# RP_Watchy.net
KiCad netlist of a schematic drawn in EAGLE
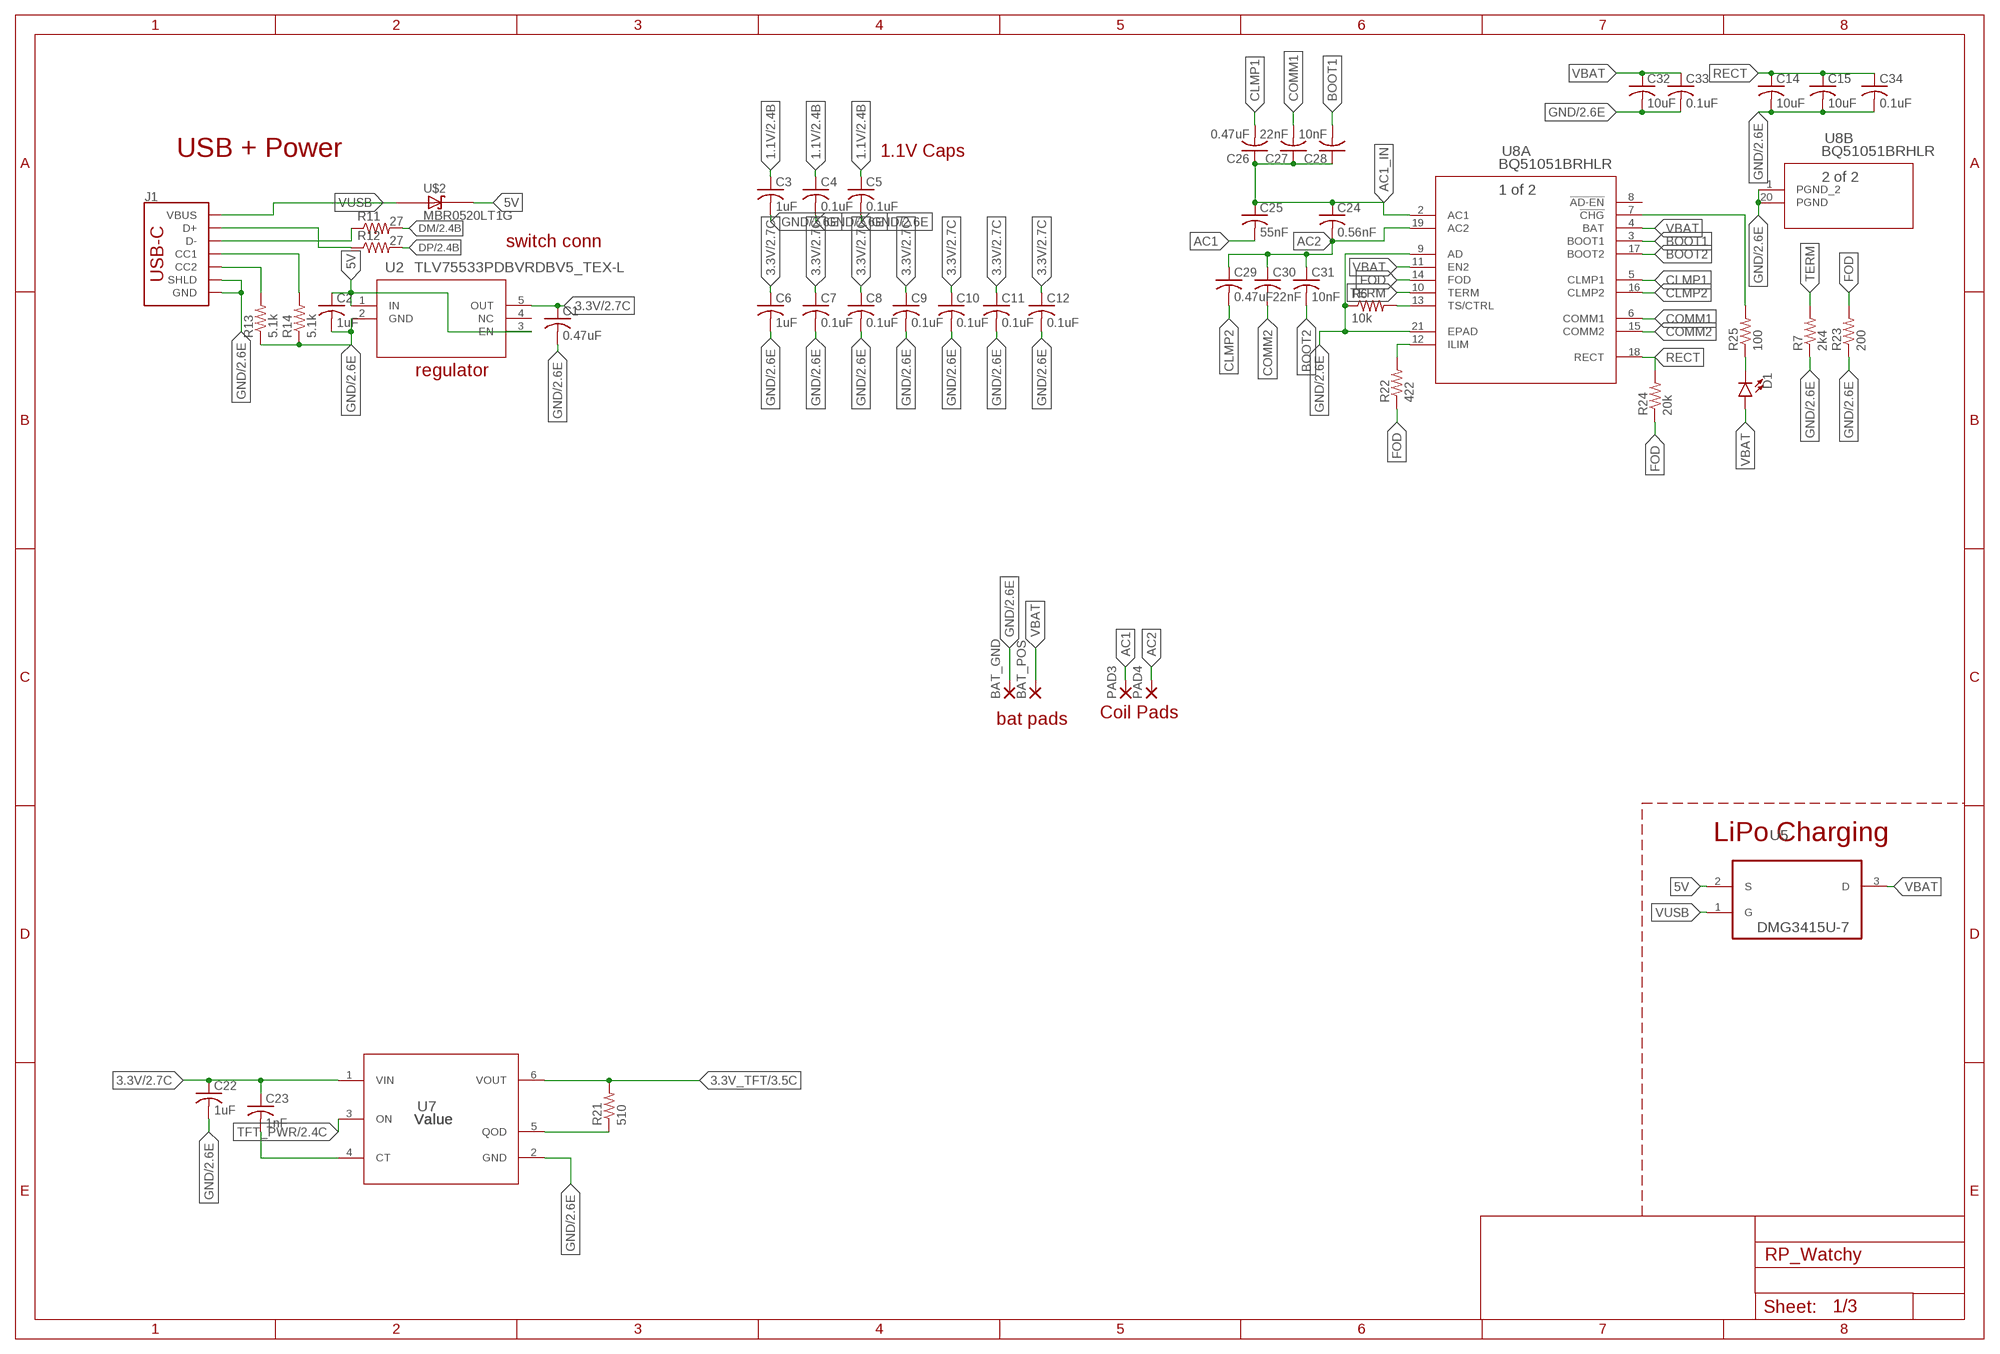
[diagram p0: schematic, sheet 1]
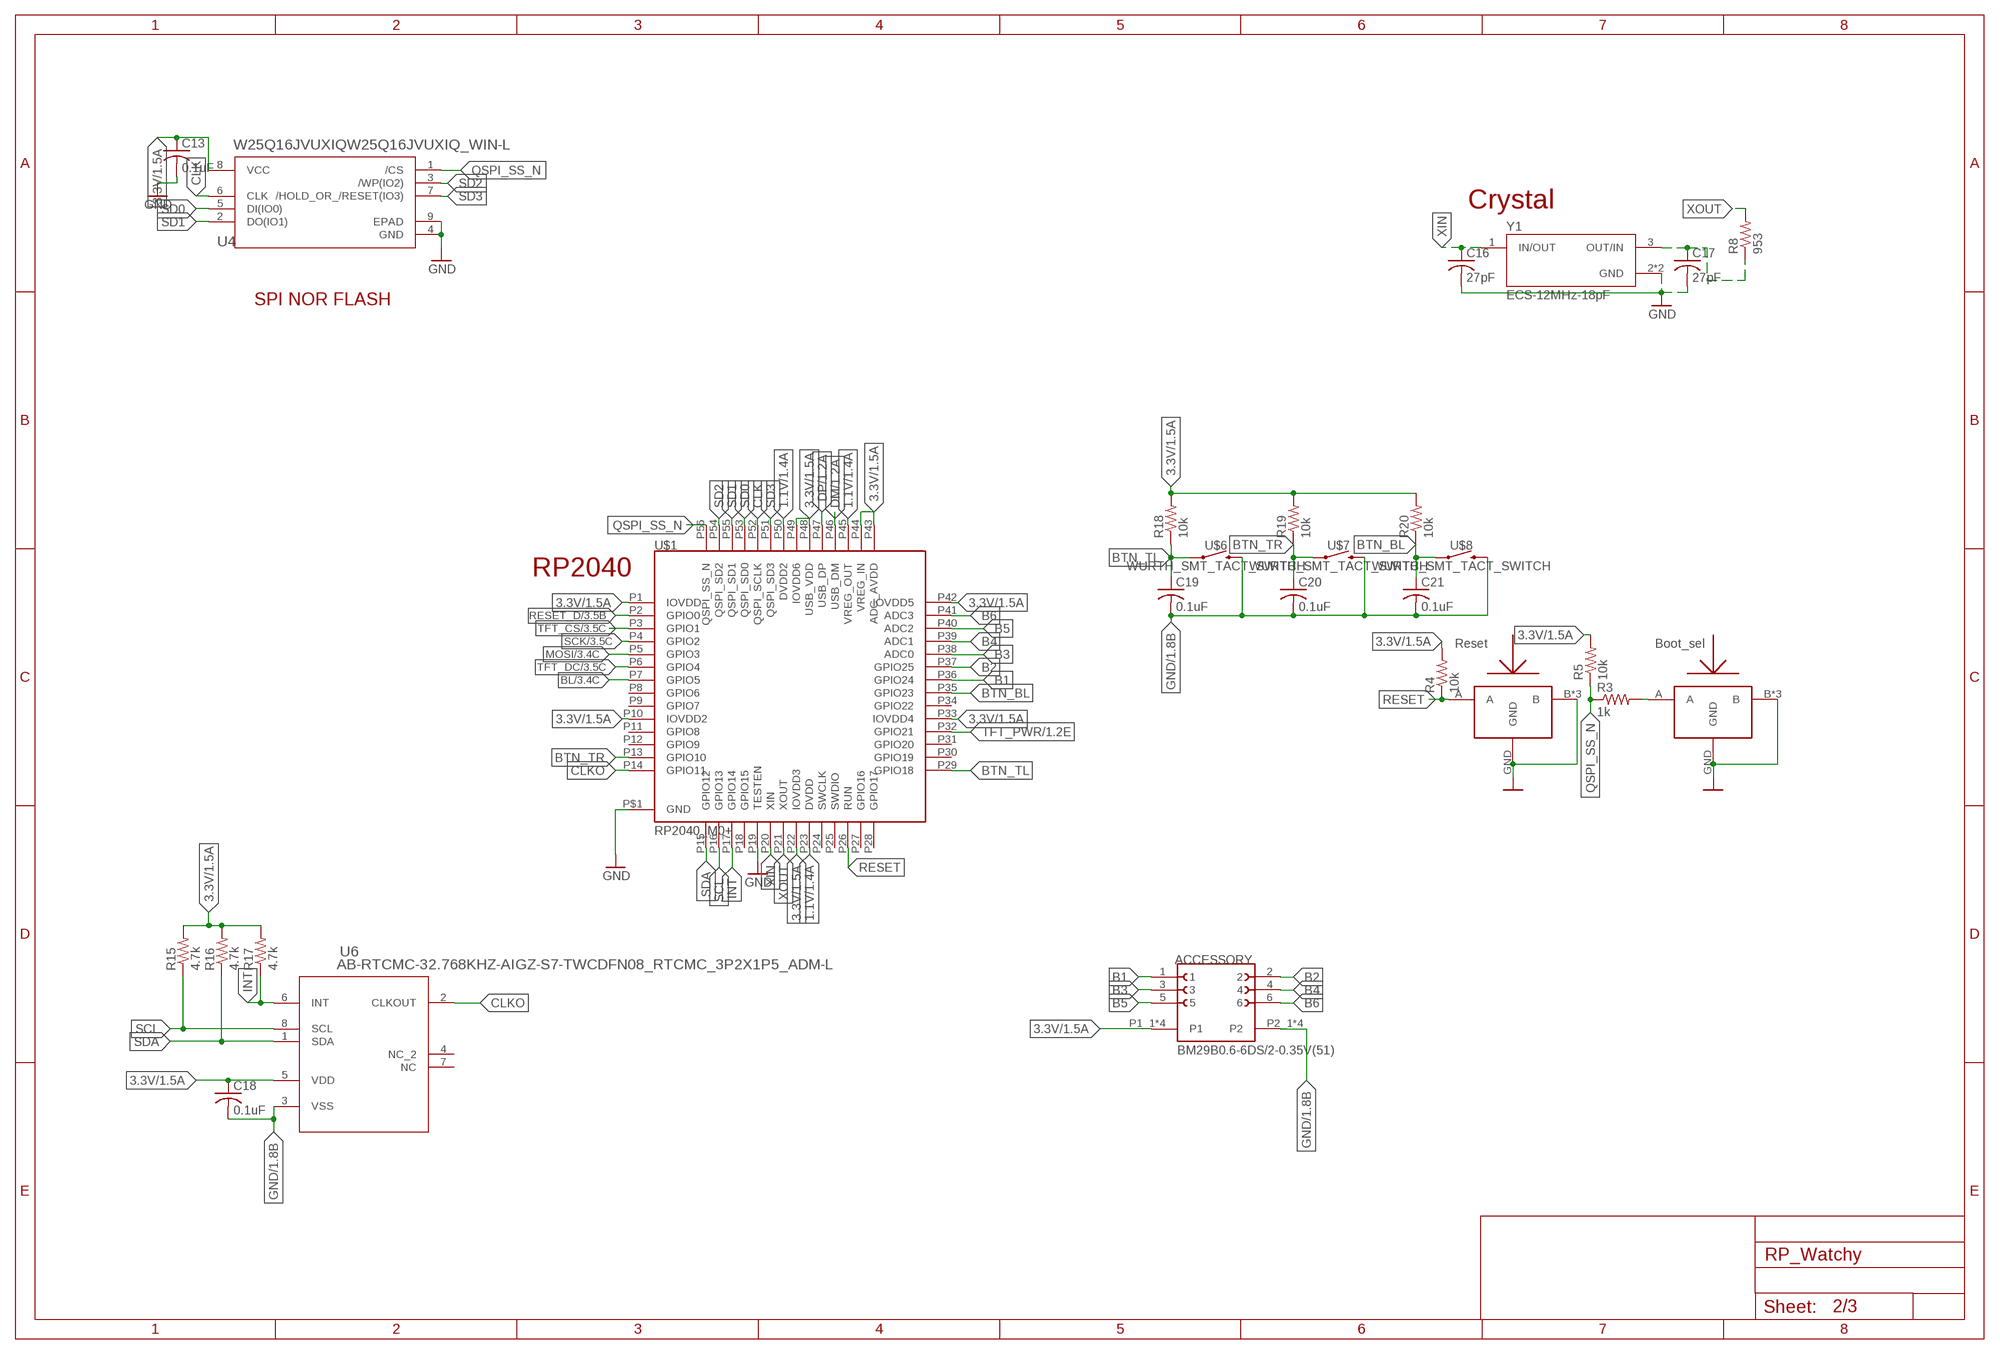
[diagram p1: schematic, sheet 2]
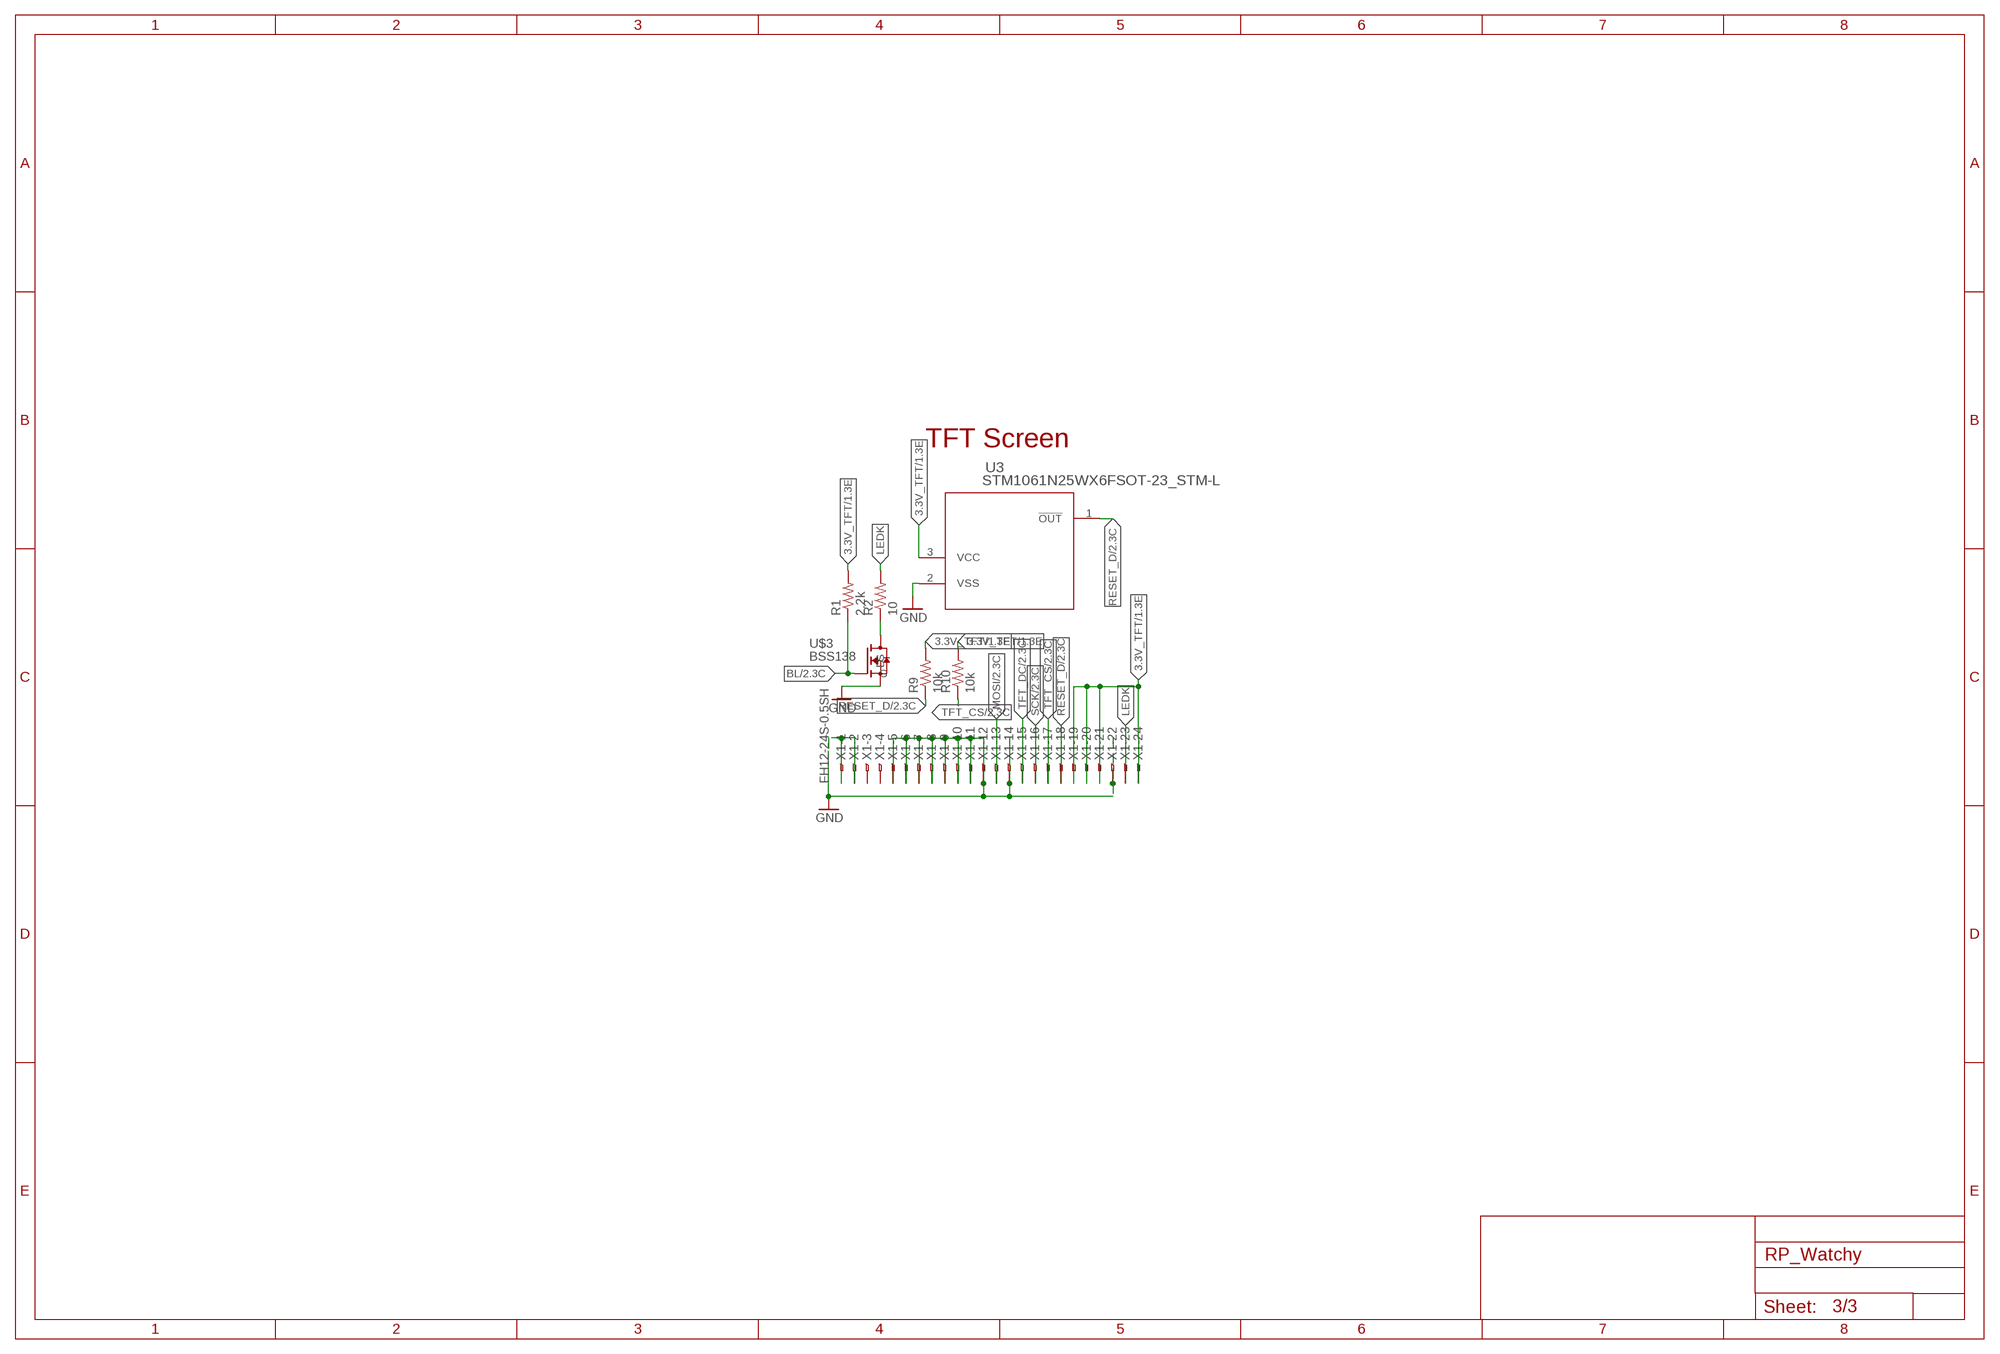
[diagram p2: schematic, sheet 3]

(export (version "E")
  (design (tool "Eeschema 10.0.6"))
  (components
    (comp (ref "BAT_GND")
      (value "SMD2")
      (footprint "eagle-import:SMD1,27-2,54")
      (libsource (lib "eagle-import") (part "SMD2"))
    )
    (comp (ref "BAT_POS")
      (value "SMD2")
      (footprint "eagle-import:SMD1,27-2,54")
      (libsource (lib "eagle-import") (part "SMD2"))
    )
    (comp (ref "C1")
      (value "0.47uF")
      (footprint "eagle-import:C0402")
      (libsource (lib "eagle-import") (part "rcl_334_C-USC0402"))
    )
    (comp (ref "C2")
      (value "1uF")
      (footprint "eagle-import:C0402")
      (libsource (lib "eagle-import") (part "rcl_334_C-USC0402"))
    )
    (comp (ref "C3")
      (value "1uF")
      (footprint "eagle-import:C0402")
      (libsource (lib "eagle-import") (part "rcl_334_C-USC0402"))
    )
    (comp (ref "C4")
      (value "0.1uF")
      (footprint "eagle-import:C0402")
      (libsource (lib "eagle-import") (part "rcl_334_C-USC0402"))
    )
    (comp (ref "C5")
      (value "0.1uF")
      (footprint "eagle-import:C0402")
      (libsource (lib "eagle-import") (part "rcl_334_C-USC0402"))
    )
    (comp (ref "C6")
      (value "1uF")
      (footprint "eagle-import:C0402")
      (libsource (lib "eagle-import") (part "rcl_334_C-USC0402"))
    )
    (comp (ref "C7")
      (value "0.1uF")
      (footprint "eagle-import:C0402")
      (libsource (lib "eagle-import") (part "rcl_334_C-USC0402"))
    )
    (comp (ref "C8")
      (value "0.1uF")
      (footprint "eagle-import:C0402")
      (libsource (lib "eagle-import") (part "rcl_334_C-USC0402"))
    )
    (comp (ref "C9")
      (value "0.1uF")
      (footprint "eagle-import:C0402")
      (libsource (lib "eagle-import") (part "rcl_334_C-USC0402"))
    )
    (comp (ref "C10")
      (value "0.1uF")
      (footprint "eagle-import:C0402")
      (libsource (lib "eagle-import") (part "rcl_334_C-USC0402"))
    )
    (comp (ref "C11")
      (value "0.1uF")
      (footprint "eagle-import:C0402")
      (libsource (lib "eagle-import") (part "rcl_334_C-USC0402"))
    )
    (comp (ref "C12")
      (value "0.1uF")
      (footprint "eagle-import:C0402")
      (libsource (lib "eagle-import") (part "rcl_334_C-USC0402"))
    )
    (comp (ref "C14")
      (value "10uF")
      (footprint "eagle-import:C0402")
      (libsource (lib "eagle-import") (part "C-USC0402"))
    )
    (comp (ref "C15")
      (value "10uF")
      (footprint "eagle-import:C0402")
      (libsource (lib "eagle-import") (part "C-USC0402"))
    )
    (comp (ref "C22")
      (value "1uF")
      (footprint "eagle-import:C0402")
      (libsource (lib "eagle-import") (part "rcl_334_C-USC0402"))
    )
    (comp (ref "C23")
      (value "1nF")
      (footprint "eagle-import:C0402")
      (libsource (lib "eagle-import") (part "rcl_334_C-USC0402"))
    )
    (comp (ref "C24")
      (value "0.56nF")
      (footprint "eagle-import:C0603")
      (libsource (lib "eagle-import") (part "C-USC0603"))
    )
    (comp (ref "C25")
      (value "55nF")
      (footprint "eagle-import:C0603")
      (libsource (lib "eagle-import") (part "C-USC0603"))
    )
    (comp (ref "C26")
      (value "0.47uF")
      (footprint "eagle-import:C0402")
      (libsource (lib "eagle-import") (part "C-USC0402"))
    )
    (comp (ref "C27")
      (value "22nF")
      (footprint "eagle-import:C0402")
      (libsource (lib "eagle-import") (part "C-USC0402"))
    )
    (comp (ref "C28")
      (value "10nF")
      (footprint "eagle-import:C0402")
      (libsource (lib "eagle-import") (part "C-USC0402"))
    )
    (comp (ref "C29")
      (value "0.47uF")
      (footprint "eagle-import:C0402")
      (libsource (lib "eagle-import") (part "C-USC0402"))
    )
    (comp (ref "C30")
      (value "22nF")
      (footprint "eagle-import:C0402")
      (libsource (lib "eagle-import") (part "C-USC0402"))
    )
    (comp (ref "C31")
      (value "10nF")
      (footprint "eagle-import:C0402")
      (libsource (lib "eagle-import") (part "C-USC0402"))
    )
    (comp (ref "C32")
      (value "10uF")
      (footprint "eagle-import:C0402")
      (libsource (lib "eagle-import") (part "C-USC0402"))
    )
    (comp (ref "C33")
      (value "0.1uF")
      (footprint "eagle-import:C0402")
      (libsource (lib "eagle-import") (part "C-USC0402"))
    )
    (comp (ref "C34")
      (value "0.1uF")
      (footprint "eagle-import:C0402")
      (libsource (lib "eagle-import") (part "C-USC0402"))
    )
    (comp (ref "D1")
      (value "LED0603")
      (footprint "eagle-import:LED-0603")
      (libsource (lib "eagle-import") (part "LED0603"))
    )
    (comp (ref "J1")
      (value "USB_C_2-LAYER_PADS")
      (footprint "eagle-import:USB-C-16P-2LAYER-PADS")
      (libsource (lib "eagle-import") (part "USB_C_2-LAYER_PADS"))
    )
    (comp (ref "PAD3")
      (value "SMD2")
      (footprint "eagle-import:SMD1,27-2,54")
      (libsource (lib "eagle-import") (part "SMD2"))
    )
    (comp (ref "PAD4")
      (value "SMD2")
      (footprint "eagle-import:SMD1,27-2,54")
      (libsource (lib "eagle-import") (part "SMD2"))
    )
    (comp (ref "R6")
      (value "10k")
      (footprint "eagle-import:R0402")
      (libsource (lib "eagle-import") (part "R-US_R0402"))
    )
    (comp (ref "R7")
      (value "2k4")
      (footprint "eagle-import:R0402")
      (libsource (lib "eagle-import") (part "R-US_R0402"))
    )
    (comp (ref "R11")
      (value "27")
      (footprint "eagle-import:R0603")
      (libsource (lib "eagle-import") (part "R-US_R0603"))
    )
    (comp (ref "R12")
      (value "27")
      (footprint "eagle-import:R0603")
      (libsource (lib "eagle-import") (part "R-US_R0603"))
    )
    (comp (ref "R13")
      (value "5.1k")
      (footprint "eagle-import:R0603")
      (libsource (lib "eagle-import") (part "R-US_R0603"))
    )
    (comp (ref "R14")
      (value "5.1k")
      (footprint "eagle-import:R0603")
      (libsource (lib "eagle-import") (part "R-US_R0603"))
    )
    (comp (ref "R21")
      (value "510")
      (footprint "eagle-import:R0402")
      (libsource (lib "eagle-import") (part "R-US_R0402"))
    )
    (comp (ref "R22")
      (value "422")
      (footprint "eagle-import:R0402")
      (libsource (lib "eagle-import") (part "R-US_R0402"))
    )
    (comp (ref "R23")
      (value "200")
      (footprint "eagle-import:R0402")
      (libsource (lib "eagle-import") (part "R-US_R0402"))
    )
    (comp (ref "R24")
      (value "20k")
      (footprint "eagle-import:R0402")
      (libsource (lib "eagle-import") (part "R-US_R0402"))
    )
    (comp (ref "R25")
      (value "100")
      (footprint "eagle-import:R0402")
      (libsource (lib "eagle-import") (part "R-US_R0402"))
    )
    (comp (ref "U$2")
      (value "MBR0520LT1G")
      (footprint "eagle-import:SOD3716X117(SOD-123)")
      (fields (field (name "MF") "ON Semiconductor"))
      (libsource (lib "eagle-import") (part "MBR0520LT1G"))
    )
    (comp (ref "U2")
      (value "TLV75533PDBVRDBV5_TEX-L")
      (footprint "eagle-import:DBV5_TEX-L")
      (fields
        (field (name "MANUFACTURER_PART_NUMBER") "TLV75533PDBVR")
        (field (name "COPYRIGHT") "Copyright (C) 2018 Accelerated Designs. All rights reserved")
      )
      (libsource (lib "eagle-import") (part "TLV75533PDBVRDBV5_TEX-L"))
    )
    (comp (ref "U5")
      (value "DMG3415U-7")
      (footprint "eagle-import:SOT95P240X105-3N")
      (fields (field (name "MF") "Diodes Inc."))
      (libsource (lib "eagle-import") (part "DMG3415U-7"))
    )
    (comp (ref "U7")
      (value "Value")
      (footprint "eagle-import:DBV0006_L")
      (fields (field (name "MANUFACTURER") "Texas Instruments") (field (name "PARTNUMBER") "TPS22917DBVR"))
      (libsource (lib "eagle-import") (part "TPS22917DBVRDBV0006_L"))
    )
    (comp (ref "U8")
      (value "BQ51051BRHLR")
      (footprint "eagle-import:RHL20_2P05X3P05")
      (fields (field (name "COPYRIGHT") "Copyright (C) 2022 Ultra Librarian. All rights reserved."))
      (libsource (lib "eagle-import") (part "BQ51051BRHLR"))
    )
    (comp (ref "ACCESSORY")
      (value "BM29B0.6-6DS/2-0.35V(51)")
      (footprint "eagle-import:HRS_BM29B0.6-6DS_2-0.35V(51)")
      (fields
        (field (name "DIGI-KEY_PART_NUMBER") "26-BM29B0.6-6DS/2-0.35V(51)TR-ND")
        (field (name "MF") "Hirose Connector")
      )
      (libsource (lib "eagle-import") (part "BM29B0.6-6DS/2-0.35V(51)"))
    )
    (comp (ref "C13")
      (value "0.1uF")
      (footprint "eagle-import:C0402")
      (libsource (lib "eagle-import") (part "rcl_334_C-USC0402"))
    )
    (comp (ref "C16")
      (value "27pF")
      (footprint "eagle-import:C0402")
      (libsource (lib "eagle-import") (part "rcl_334_C-USC0402"))
    )
    (comp (ref "C17")
      (value "27pF")
      (footprint "eagle-import:C0402")
      (libsource (lib "eagle-import") (part "rcl_334_C-USC0402"))
    )
    (comp (ref "C18")
      (value "0.1uF")
      (footprint "eagle-import:C0402")
      (libsource (lib "eagle-import") (part "rcl_334_C-USC0402"))
    )
    (comp (ref "C19")
      (value "0.1uF")
      (footprint "eagle-import:C0402")
      (libsource (lib "eagle-import") (part "rcl_334_C-USC0402"))
    )
    (comp (ref "C20")
      (value "0.1uF")
      (footprint "eagle-import:C0402")
      (libsource (lib "eagle-import") (part "rcl_334_C-USC0402"))
    )
    (comp (ref "C21")
      (value "0.1uF")
      (footprint "eagle-import:C0402")
      (libsource (lib "eagle-import") (part "rcl_334_C-USC0402"))
    )
    (comp (ref "R3")
      (value "1k")
      (footprint "eagle-import:R0402")
      (libsource (lib "eagle-import") (part "R-US_R0402"))
    )
    (comp (ref "R4")
      (value "10k")
      (footprint "eagle-import:R0402")
      (libsource (lib "eagle-import") (part "R-US_R0402"))
    )
    (comp (ref "R5")
      (value "10k")
      (footprint "eagle-import:R0402")
      (libsource (lib "eagle-import") (part "R-US_R0402"))
    )
    (comp (ref "R8")
      (value "953")
      (footprint "eagle-import:R0402")
      (libsource (lib "eagle-import") (part "R-US_R0402"))
    )
    (comp (ref "R15")
      (value "4.7k")
      (footprint "eagle-import:R0402")
      (libsource (lib "eagle-import") (part "R-US_R0402"))
    )
    (comp (ref "R16")
      (value "4.7k")
      (footprint "eagle-import:R0402")
      (libsource (lib "eagle-import") (part "R-US_R0402"))
    )
    (comp (ref "R17")
      (value "4.7k")
      (footprint "eagle-import:R0402")
      (libsource (lib "eagle-import") (part "R-US_R0402"))
    )
    (comp (ref "R18")
      (value "10k")
      (footprint "eagle-import:R0402")
      (libsource (lib "eagle-import") (part "R-US_R0402"))
    )
    (comp (ref "R19")
      (value "10k")
      (footprint "eagle-import:R0402")
      (libsource (lib "eagle-import") (part "R-US_R0402"))
    )
    (comp (ref "R20")
      (value "10k")
      (footprint "eagle-import:R0402")
      (libsource (lib "eagle-import") (part "R-US_R0402"))
    )
    (comp (ref "U$1")
      (value "RP2040_M0+")
      (footprint "eagle-import:QFN-56")
      (libsource (lib "eagle-import") (part "RP2040_M0+"))
    )
    (comp (ref "U$4")
      (value "SOF-232HST")
      (footprint "eagle-import:3.3X2.9")
      (libsource (lib "eagle-import") (part "SOF-232HST"))
    )
    (comp (ref "U$5")
      (value "SOF-232HST")
      (footprint "eagle-import:3.3X2.9")
      (libsource (lib "eagle-import") (part "SOF-232HST"))
    )
    (comp (ref "U$6")
      (value "WURTH_SMT_TACT_SWITCH")
      (footprint "eagle-import:SIDE_MOUNT_SWITCH")
      (libsource (lib "eagle-import") (part "WURTH_SMT_TACT_SWITCH"))
    )
    (comp (ref "U$7")
      (value "WURTH_SMT_TACT_SWITCH")
      (footprint "eagle-import:SIDE_MOUNT_SWITCH")
      (libsource (lib "eagle-import") (part "WURTH_SMT_TACT_SWITCH"))
    )
    (comp (ref "U$8")
      (value "WURTH_SMT_TACT_SWITCH")
      (footprint "eagle-import:SIDE_MOUNT_SWITCH")
      (libsource (lib "eagle-import") (part "WURTH_SMT_TACT_SWITCH"))
    )
    (comp (ref "U4")
      (value "W25Q16JVUXIQW25Q16JVUXIQ_WIN-L")
      (footprint "eagle-import:W25Q16JVUXIQ_WIN-L")
      (fields
        (field (name "MANUFACTURER_PART_NUMBER") "W25Q16JVUXIQ")
        (field (name "COPYRIGHT") "Copyright (C) 2018 Accelerated Designs. All rights reserved")
      )
      (libsource (lib "eagle-import") (part "W25Q16JVUXIQW25Q16JVUXIQ_WIN-L"))
    )
    (comp (ref "U6")
      (value "AB-RTCMC-32.768KHZ-AIGZ-S7-TWCDFN08_RTCMC_3P2X1P5_ADM-L")
      (footprint "eagle-import:WCDFN08_RTCMC_3P2X1P5_ADM-L")
      (fields
        (field (name "MANUFACTURER_PART_NUMBER") "AB-RTCMC-32.768KHZ-AIGZ-S7-T")
        (field (name "COPYRIGHT") "Copyright (C) 2022 Ultra Librarian. All rights reserved.")
      )
      (libsource (lib "eagle-import") (part "AB-RTCMC-32.768KHZ-AIGZ-S7-TWCDFN08_RTCMC_3P2X1P5_ADM-L"))
    )
    (comp (ref "Y1")
      (value "ECS-12MHz-18pF")
      (footprint "eagle-import:XTAL_ECS-327ATQMV-AS-TR")
      (fields
        (field (name "DIGI-KEY_PART_NUMBER") "XC2826CT-ND")
        (field (name "MF") "ECS Inc.")
        (field (name "MP") "ECS-327ATQMV-AS-TR")
      )
      (libsource (lib "eagle-import") (part "ECS-327ATQMV-AS-TR"))
    )
    (comp (ref "R1")
      (value "2.2k")
      (footprint "eagle-import:R0603")
      (libsource (lib "eagle-import") (part "R-US_R0603"))
    )
    (comp (ref "R2")
      (value "10")
      (footprint "eagle-import:R0402")
      (libsource (lib "eagle-import") (part "R-US_R0402"))
    )
    (comp (ref "R9")
      (value "10k")
      (footprint "eagle-import:R0402")
      (libsource (lib "eagle-import") (part "R-US_R0402"))
    )
    (comp (ref "R10")
      (value "10k")
      (footprint "eagle-import:R0402")
      (libsource (lib "eagle-import") (part "R-US_R0402"))
    )
    (comp (ref "U$3")
      (value "BSS138")
      (footprint "eagle-import:BSS138")
      (fields (field (name "MF") "MICROSS/On Semiconductor"))
      (libsource (lib "eagle-import") (part "BSS138"))
    )
    (comp (ref "U3")
      (value "STM1061N25WX6FSOT-23_STM-L")
      (footprint "eagle-import:SOT-23_STM-L")
      (fields
        (field (name "MANUFACTURER_PART_NUMBER") "STM1061N25WX6F")
        (field (name "COPYRIGHT") "Copyright (C) 2021 Ultra Librarian. All rights reserved.")
      )
      (libsource (lib "eagle-import") (part "STM1061N25WX6FSOT-23_STM-L"))
    )
    (comp (ref "X1")
      (value "FH12-24S-0.5SH")
      (footprint "eagle-import:FH12-24S-0.5SH")
      (fields (field (name "MPN") "FH12-24S-0.5SH(55)"))
      (libsource (lib "eagle-import") (part "FH12-24S-0.5SH"))
    )
  )
  (nets
    (net (code "1") (name "1.1V") (class "Default")
      (node (ref "C3") (pin "1") (pinfunction "1_1") (pintype "passive"))
      (node (ref "C4") (pin "1") (pinfunction "1_1") (pintype "passive"))
      (node (ref "C5") (pin "1") (pinfunction "1_1") (pintype "passive"))
      (node (ref "U$1") (pin "P23") (pinfunction "DVDD_P23") (pintype "bidirectional"))
      (node (ref "U$1") (pin "P45") (pinfunction "VREG_OUT_P45") (pintype "bidirectional"))
      (node (ref "U$1") (pin "P50") (pinfunction "DVDD2_P50") (pintype "bidirectional"))
    )
    (net (code "2") (name "3.3V") (class "Default")
      (node (ref "ACCESSORY") (pin "P1_1") (pinfunction "P1_P1_1") (pintype "power_in"))
      (node (ref "ACCESSORY") (pin "P1_2") (pinfunction "P1_P1_2") (pintype "power_in"))
      (node (ref "ACCESSORY") (pin "P1_3") (pinfunction "P1_P1_3") (pintype "power_in"))
      (node (ref "ACCESSORY") (pin "P1_4") (pinfunction "P1_P1_4") (pintype "power_in"))
      (node (ref "C1") (pin "1") (pinfunction "1_1") (pintype "passive"))
      (node (ref "C10") (pin "1") (pinfunction "1_1") (pintype "passive"))
      (node (ref "C11") (pin "1") (pinfunction "1_1") (pintype "passive"))
      (node (ref "C12") (pin "1") (pinfunction "1_1") (pintype "passive"))
      (node (ref "C13") (pin "1") (pinfunction "1_1") (pintype "passive"))
      (node (ref "C18") (pin "1") (pinfunction "1_1") (pintype "passive"))
      (node (ref "C22") (pin "1") (pinfunction "1_1") (pintype "passive"))
      (node (ref "C23") (pin "1") (pinfunction "1_1") (pintype "passive"))
      (node (ref "C6") (pin "1") (pinfunction "1_1") (pintype "passive"))
      (node (ref "C7") (pin "1") (pinfunction "1_1") (pintype "passive"))
      (node (ref "C8") (pin "1") (pinfunction "1_1") (pintype "passive"))
      (node (ref "C9") (pin "1") (pinfunction "1_1") (pintype "passive"))
      (node (ref "R15") (pin "2") (pinfunction "2_2") (pintype "passive"))
      (node (ref "R16") (pin "2") (pinfunction "2_2") (pintype "passive"))
      (node (ref "R17") (pin "2") (pinfunction "2_2") (pintype "passive"))
      (node (ref "R18") (pin "2") (pinfunction "2_2") (pintype "passive"))
      (node (ref "R19") (pin "2") (pinfunction "2_2") (pintype "passive"))
      (node (ref "R20") (pin "2") (pinfunction "2_2") (pintype "passive"))
      (node (ref "R4") (pin "2") (pinfunction "2_2") (pintype "passive"))
      (node (ref "R5") (pin "2") (pinfunction "2_2") (pintype "passive"))
      (node (ref "U$1") (pin "P1") (pinfunction "IOVDD_P1") (pintype "bidirectional"))
      (node (ref "U$1") (pin "P10") (pinfunction "IOVDD2_P10") (pintype "bidirectional"))
      (node (ref "U$1") (pin "P22") (pinfunction "IOVDD3_P22") (pintype "bidirectional"))
      (node (ref "U$1") (pin "P33") (pinfunction "IOVDD4_P33") (pintype "bidirectional"))
      (node (ref "U$1") (pin "P42") (pinfunction "IOVDD5_P42") (pintype "bidirectional"))
      (node (ref "U$1") (pin "P43") (pinfunction "ADC_AVDD_P43") (pintype "bidirectional"))
      (node (ref "U$1") (pin "P44") (pinfunction "VREG_IN_P44") (pintype "bidirectional"))
      (node (ref "U$1") (pin "P48") (pinfunction "USB_VDD_P48") (pintype "bidirectional"))
      (node (ref "U$1") (pin "P49") (pinfunction "IOVDD6_P49") (pintype "bidirectional"))
      (node (ref "U2") (pin "5") (pinfunction "OUT_5") (pintype "output"))
      (node (ref "U4") (pin "8") (pinfunction "VCC_8") (pintype "passive"))
      (node (ref "U6") (pin "5") (pinfunction "VDD_5") (pintype "power_in"))
      (node (ref "U7") (pin "1") (pinfunction "VIN_1") (pintype "power_in"))
    )
    (net (code "3") (name "3.3V_TFT") (class "Default")
      (node (ref "R1") (pin "2") (pinfunction "2_2") (pintype "passive"))
      (node (ref "R10") (pin "2") (pinfunction "2_2") (pintype "passive"))
      (node (ref "R21") (pin "2") (pinfunction "2_2") (pintype "passive"))
      (node (ref "R9") (pin "2") (pinfunction "2_2") (pintype "passive"))
      (node (ref "U3") (pin "3") (pinfunction "VCC_3") (pintype "power_in"))
      (node (ref "U7") (pin "6") (pinfunction "VOUT_6") (pintype "power_in"))
      (node (ref "X1") (pin "19") (pinfunction "1_19") (pintype "passive"))
      (node (ref "X1") (pin "20") (pinfunction "1_20") (pintype "passive"))
      (node (ref "X1") (pin "21") (pinfunction "1_21") (pintype "passive"))
      (node (ref "X1") (pin "24") (pinfunction "1_24") (pintype "passive"))
    )
    (net (code "4") (name "5V") (class "Default")
      (node (ref "C2") (pin "1") (pinfunction "1_1") (pintype "passive"))
      (node (ref "U$2") (pin "1") (pinfunction "C_1") (pintype "passive"))
      (node (ref "U2") (pin "1") (pinfunction "IN_1") (pintype "input"))
      (node (ref "U2") (pin "3") (pinfunction "EN_3") (pintype "input"))
      (node (ref "U5") (pin "2") (pinfunction "S_2") (pintype "passive"))
    )
    (net (code "5") (name "AC1") (class "Default")
      (node (ref "C25") (pin "2") (pinfunction "2_2") (pintype "passive"))
      (node (ref "PAD3") (pin "1") (pinfunction "P_1") (pintype "passive"))
    )
    (net (code "6") (name "AC1_IN") (class "Default")
      (node (ref "C24") (pin "1") (pinfunction "1_1") (pintype "passive"))
      (node (ref "C25") (pin "1") (pinfunction "1_1") (pintype "passive"))
      (node (ref "C26") (pin "1") (pinfunction "1_1") (pintype "passive"))
      (node (ref "C27") (pin "1") (pinfunction "1_1") (pintype "passive"))
      (node (ref "C28") (pin "1") (pinfunction "1_1") (pintype "passive"))
      (node (ref "U8") (pin "2") (pinfunction "AC1_2") (pintype "input"))
    )
    (net (code "7") (name "AC2") (class "Default")
      (node (ref "C24") (pin "2") (pinfunction "2_2") (pintype "passive"))
      (node (ref "C29") (pin "1") (pinfunction "1_1") (pintype "passive"))
      (node (ref "C30") (pin "1") (pinfunction "1_1") (pintype "passive"))
      (node (ref "C31") (pin "1") (pinfunction "1_1") (pintype "passive"))
      (node (ref "PAD4") (pin "1") (pinfunction "P_1") (pintype "passive"))
      (node (ref "U8") (pin "19") (pinfunction "AC2_19") (pintype "input"))
    )
    (net (code "8") (name "B1") (class "Default")
      (node (ref "ACCESSORY") (pin "1") (pinfunction "1_1") (pintype "passive"))
      (node (ref "U$1") (pin "P36") (pinfunction "GPIO24_P36") (pintype "bidirectional"))
    )
    (net (code "9") (name "B2") (class "Default")
      (node (ref "ACCESSORY") (pin "2") (pinfunction "2_2") (pintype "passive"))
      (node (ref "U$1") (pin "P37") (pinfunction "GPIO25_P37") (pintype "bidirectional"))
    )
    (net (code "10") (name "B3") (class "Default")
      (node (ref "ACCESSORY") (pin "3") (pinfunction "3_3") (pintype "passive"))
      (node (ref "U$1") (pin "P38") (pinfunction "ADC0_P38") (pintype "bidirectional"))
    )
    (net (code "11") (name "B4") (class "Default")
      (node (ref "ACCESSORY") (pin "4") (pinfunction "4_4") (pintype "passive"))
      (node (ref "U$1") (pin "P39") (pinfunction "ADC1_P39") (pintype "bidirectional"))
    )
    (net (code "12") (name "B5") (class "Default")
      (node (ref "ACCESSORY") (pin "5") (pinfunction "5_5") (pintype "passive"))
      (node (ref "U$1") (pin "P40") (pinfunction "ADC2_P40") (pintype "bidirectional"))
    )
    (net (code "13") (name "B6") (class "Default")
      (node (ref "ACCESSORY") (pin "6") (pinfunction "6_6") (pintype "passive"))
      (node (ref "U$1") (pin "P41") (pinfunction "ADC3_P41") (pintype "bidirectional"))
    )
    (net (code "14") (name "BL") (class "Default")
      (node (ref "R1") (pin "1") (pinfunction "1_1") (pintype "passive"))
      (node (ref "U$1") (pin "P7") (pinfunction "GPIO5_P7") (pintype "bidirectional"))
      (node (ref "U$3") (pin "G") (pinfunction "G_G") (pintype "passive"))
    )
    (net (code "15") (name "BOOT1") (class "Default")
      (node (ref "C28") (pin "2") (pinfunction "2_2") (pintype "passive"))
      (node (ref "U8") (pin "3") (pinfunction "BOOT1_3") (pintype "output"))
    )
    (net (code "16") (name "BOOT2") (class "Default")
      (node (ref "C31") (pin "2") (pinfunction "2_2") (pintype "passive"))
      (node (ref "U8") (pin "17") (pinfunction "BOOT2_17") (pintype "output"))
    )
    (net (code "17") (name "BTN_BL") (class "Default")
      (node (ref "C21") (pin "1") (pinfunction "1_1") (pintype "passive"))
      (node (ref "R20") (pin "1") (pinfunction "1_1") (pintype "passive"))
      (node (ref "U$1") (pin "P35") (pinfunction "GPIO23_P35") (pintype "bidirectional"))
      (node (ref "U$8") (pin "1") (pinfunction "1_1") (pintype "passive"))
    )
    (net (code "18") (name "BTN_TL") (class "Default")
      (node (ref "C19") (pin "1") (pinfunction "1_1") (pintype "passive"))
      (node (ref "R18") (pin "1") (pinfunction "1_1") (pintype "passive"))
      (node (ref "U$1") (pin "P29") (pinfunction "GPIO18_P29") (pintype "bidirectional"))
      (node (ref "U$6") (pin "1") (pinfunction "1_1") (pintype "passive"))
    )
    (net (code "19") (name "BTN_TR") (class "Default")
      (node (ref "C20") (pin "1") (pinfunction "1_1") (pintype "passive"))
      (node (ref "R19") (pin "1") (pinfunction "1_1") (pintype "passive"))
      (node (ref "U$1") (pin "P13") (pinfunction "GPIO10_P13") (pintype "bidirectional"))
      (node (ref "U$7") (pin "1") (pinfunction "1_1") (pintype "passive"))
    )
    (net (code "20") (name "CLK") (class "Default")
      (node (ref "U$1") (pin "P52") (pinfunction "QSPI_SCLK_P52") (pintype "bidirectional"))
      (node (ref "U4") (pin "6") (pinfunction "CLK_6") (pintype "passive"))
    )
    (net (code "21") (name "CLKO") (class "Default")
      (node (ref "U$1") (pin "P14") (pinfunction "GPIO11_P14") (pintype "bidirectional"))
      (node (ref "U6") (pin "2") (pinfunction "CLKOUT_2") (pintype "output"))
    )
    (net (code "22") (name "CLMP1") (class "Default")
      (node (ref "C26") (pin "2") (pinfunction "2_2") (pintype "passive"))
      (node (ref "U8") (pin "5") (pinfunction "CLMP1_5") (pintype "output"))
    )
    (net (code "23") (name "CLMP2") (class "Default")
      (node (ref "C29") (pin "2") (pinfunction "2_2") (pintype "passive"))
      (node (ref "U8") (pin "16") (pinfunction "CLMP2_16") (pintype "output"))
    )
    (net (code "24") (name "COMM1") (class "Default")
      (node (ref "C27") (pin "2") (pinfunction "2_2") (pintype "passive"))
      (node (ref "U8") (pin "6") (pinfunction "COMM1_6") (pintype "output"))
    )
    (net (code "25") (name "COMM2") (class "Default")
      (node (ref "C30") (pin "2") (pinfunction "2_2") (pintype "passive"))
      (node (ref "U8") (pin "15") (pinfunction "COMM2_15") (pintype "output"))
    )
    (net (code "26") (name "DM") (class "Default")
      (node (ref "R11") (pin "2") (pinfunction "2_2") (pintype "passive"))
      (node (ref "U$1") (pin "P46") (pinfunction "USB_DM_P46") (pintype "bidirectional"))
    )
    (net (code "27") (name "DP") (class "Default")
      (node (ref "R12") (pin "2") (pinfunction "2_2") (pintype "passive"))
      (node (ref "U$1") (pin "P47") (pinfunction "USB_DP_P47") (pintype "bidirectional"))
    )
    (net (code "28") (name "FOD") (class "Default")
      (node (ref "R22") (pin "1") (pinfunction "1_1") (pintype "passive"))
      (node (ref "R23") (pin "2") (pinfunction "2_2") (pintype "passive"))
      (node (ref "R24") (pin "1") (pinfunction "1_1") (pintype "passive"))
      (node (ref "U8") (pin "14") (pinfunction "FOD_14") (pintype "input"))
    )
    (net (code "29") (name "GND") (class "Default")
      (node (ref "ACCESSORY") (pin "P2_1") (pinfunction "P2_P2_1") (pintype "power_in"))
      (node (ref "ACCESSORY") (pin "P2_2") (pinfunction "P2_P2_2") (pintype "power_in"))
      (node (ref "ACCESSORY") (pin "P2_3") (pinfunction "P2_P2_3") (pintype "power_in"))
      (node (ref "ACCESSORY") (pin "P2_4") (pinfunction "P2_P2_4") (pintype "power_in"))
      (node (ref "BAT_GND") (pin "1") (pinfunction "P_1") (pintype "passive"))
      (node (ref "C1") (pin "2") (pinfunction "2_2") (pintype "passive"))
      (node (ref "C10") (pin "2") (pinfunction "2_2") (pintype "passive"))
      (node (ref "C11") (pin "2") (pinfunction "2_2") (pintype "passive"))
      (node (ref "C12") (pin "2") (pinfunction "2_2") (pintype "passive"))
      (node (ref "C13") (pin "2") (pinfunction "2_2") (pintype "passive"))
      (node (ref "C14") (pin "2") (pinfunction "2_2") (pintype "passive"))
      (node (ref "C15") (pin "2") (pinfunction "2_2") (pintype "passive"))
      (node (ref "C16") (pin "2") (pinfunction "2_2") (pintype "passive"))
      (node (ref "C17") (pin "2") (pinfunction "2_2") (pintype "passive"))
      (node (ref "C18") (pin "2") (pinfunction "2_2") (pintype "passive"))
      (node (ref "C19") (pin "2") (pinfunction "2_2") (pintype "passive"))
      (node (ref "C2") (pin "2") (pinfunction "2_2") (pintype "passive"))
      (node (ref "C20") (pin "2") (pinfunction "2_2") (pintype "passive"))
      (node (ref "C21") (pin "2") (pinfunction "2_2") (pintype "passive"))
      (node (ref "C22") (pin "2") (pinfunction "2_2") (pintype "passive"))
      (node (ref "C3") (pin "2") (pinfunction "2_2") (pintype "passive"))
      (node (ref "C32") (pin "2") (pinfunction "2_2") (pintype "passive"))
      (node (ref "C33") (pin "2") (pinfunction "2_2") (pintype "passive"))
      (node (ref "C34") (pin "2") (pinfunction "2_2") (pintype "passive"))
      (node (ref "C4") (pin "2") (pinfunction "2_2") (pintype "passive"))
      (node (ref "C5") (pin "2") (pinfunction "2_2") (pintype "passive"))
      (node (ref "C6") (pin "2") (pinfunction "2_2") (pintype "passive"))
      (node (ref "C7") (pin "2") (pinfunction "2_2") (pintype "passive"))
      (node (ref "C8") (pin "2") (pinfunction "2_2") (pintype "passive"))
      (node (ref "C9") (pin "2") (pinfunction "2_2") (pintype "passive"))
      (node (ref "J1") (pin "GND") (pinfunction "GND_GND") (pintype "bidirectional"))
      (node (ref "J1") (pin "GND2") (pinfunction "GND_GND2") (pintype "bidirectional"))
      (node (ref "J1") (pin "P$1") (pinfunction "SHLD_P$1") (pintype "bidirectional"))
      (node (ref "J1") (pin "P$2") (pinfunction "SHLD_P$2") (pintype "bidirectional"))
      (node (ref "J1") (pin "P$3") (pinfunction "SHLD_P$3") (pintype "bidirectional"))
      (node (ref "J1") (pin "P$4") (pinfunction "SHLD_P$4") (pintype "bidirectional"))
      (node (ref "J1") (pin "SHLD1") (pinfunction "SHLD_SHLD1") (pintype "bidirectional"))
      (node (ref "J1") (pin "SHLD2") (pinfunction "SHLD_SHLD2") (pintype "bidirectional"))
      (node (ref "J1") (pin "SHLD3") (pinfunction "SHLD_SHLD3") (pintype "bidirectional"))
      (node (ref "J1") (pin "SHLD4") (pinfunction "SHLD_SHLD4") (pintype "bidirectional"))
      (node (ref "R13") (pin "1") (pinfunction "1_1") (pintype "passive"))
      (node (ref "R14") (pin "1") (pinfunction "1_1") (pintype "passive"))
      (node (ref "R23") (pin "1") (pinfunction "1_1") (pintype "passive"))
      (node (ref "R6") (pin "1") (pinfunction "1_1") (pintype "passive"))
      (node (ref "R7") (pin "1") (pinfunction "1_1") (pintype "passive"))
      (node (ref "U$1") (pin "P$1") (pinfunction "GND_P$1") (pintype "bidirectional"))
      (node (ref "U$1") (pin "P19") (pinfunction "TESTEN_P19") (pintype "bidirectional"))
      (node (ref "U$3") (pin "S") (pinfunction "S_S") (pintype "passive"))
      (node (ref "U$4") (pin "B") (pinfunction "B_B") (pintype "bidirectional"))
      (node (ref "U$4") (pin "B2") (pinfunction "B_B2") (pintype "bidirectional"))
      (node (ref "U$4") (pin "B3") (pinfunction "B_B3") (pintype "bidirectional"))
      (node (ref "U$4") (pin "GND") (pinfunction "GND_GND") (pintype "bidirectional"))
      (node (ref "U$5") (pin "B") (pinfunction "B_B") (pintype "bidirectional"))
      (node (ref "U$5") (pin "B2") (pinfunction "B_B2") (pintype "bidirectional"))
      (node (ref "U$5") (pin "B3") (pinfunction "B_B3") (pintype "bidirectional"))
      (node (ref "U$5") (pin "GND") (pinfunction "GND_GND") (pintype "bidirectional"))
      (node (ref "U$6") (pin "2") (pinfunction "2_2") (pintype "passive"))
      (node (ref "U$7") (pin "2") (pinfunction "2_2") (pintype "passive"))
      (node (ref "U$8") (pin "2") (pinfunction "2_2") (pintype "passive"))
      (node (ref "U2") (pin "2") (pinfunction "GND_2") (pintype "power_in"))
      (node (ref "U3") (pin "2") (pinfunction "VSS_2") (pintype "power_in"))
      (node (ref "U4") (pin "4") (pinfunction "GND_4") (pintype "passive"))
      (node (ref "U4") (pin "9") (pinfunction "EPAD_9") (pintype "passive"))
      (node (ref "U6") (pin "3") (pinfunction "VSS_3") (pintype "passive"))
      (node (ref "U7") (pin "2") (pinfunction "GND_2") (pintype "power_in"))
      (node (ref "U8") (pin "1") (pinfunction "PGND_2_1") (pintype "power_in"))
      (node (ref "U8") (pin "20") (pinfunction "PGND_20") (pintype "power_in"))
      (node (ref "U8") (pin "21") (pinfunction "EPAD_21") (pintype "passive"))
      (node (ref "U8") (pin "9") (pinfunction "AD_9") (pintype "input"))
      (node (ref "X1") (pin "1") (pinfunction "1_1") (pintype "passive"))
      (node (ref "X1") (pin "10") (pinfunction "1_10") (pintype "passive"))
      (node (ref "X1") (pin "11") (pinfunction "1_11") (pintype "passive"))
      (node (ref "X1") (pin "12") (pinfunction "1_12") (pintype "passive"))
      (node (ref "X1") (pin "14") (pinfunction "1_14") (pintype "passive"))
      (node (ref "X1") (pin "2") (pinfunction "1_2") (pintype "passive"))
      (node (ref "X1") (pin "22") (pinfunction "1_22") (pintype "passive"))
      (node (ref "X1") (pin "5") (pinfunction "1_5") (pintype "passive"))
      (node (ref "X1") (pin "6") (pinfunction "1_6") (pintype "passive"))
      (node (ref "X1") (pin "7") (pinfunction "1_7") (pintype "passive"))
      (node (ref "X1") (pin "8") (pinfunction "1_8") (pintype "passive"))
      (node (ref "X1") (pin "9") (pinfunction "1_9") (pintype "passive"))
      (node (ref "Y1") (pin "2") (pinfunction "GND_2") (pintype "power_in"))
      (node (ref "Y1") (pin "4") (pinfunction "GND_4") (pintype "power_in"))
    )
    (net (code "30") (name "INT") (class "Default")
      (node (ref "R17") (pin "1") (pinfunction "1_1") (pintype "passive"))
      (node (ref "U$1") (pin "P17") (pinfunction "GPIO14_P17") (pintype "bidirectional"))
      (node (ref "U6") (pin "6") (pinfunction "INT_6") (pintype "input"))
    )
    (net (code "31") (name "LEDK") (class "Default")
      (node (ref "R2") (pin "2") (pinfunction "2_2") (pintype "passive"))
      (node (ref "X1") (pin "23") (pinfunction "1_23") (pintype "passive"))
    )
    (net (code "32") (name "MOSI") (class "Default")
      (node (ref "U$1") (pin "P5") (pinfunction "GPIO3_P5") (pintype "bidirectional"))
      (node (ref "X1") (pin "13") (pinfunction "1_13") (pintype "passive"))
    )
    (net (code "33") (name "Net-(D1-PadC)") (class "Default")
      (node (ref "D1") (pin "C") (pinfunction "C_C") (pintype "passive"))
      (node (ref "R25") (pin "1") (pinfunction "1_1") (pintype "passive"))
    )
    (net (code "34") (name "Net-(J1-CC1)") (class "Default")
      (node (ref "J1") (pin "A5") (pinfunction "CC1_A5") (pintype "bidirectional"))
      (node (ref "R14") (pin "2") (pinfunction "2_2") (pintype "passive"))
    )
    (net (code "35") (name "Net-(J1-CC2)") (class "Default")
      (node (ref "J1") (pin "B5") (pinfunction "CC2_B5") (pintype "bidirectional"))
      (node (ref "R13") (pin "2") (pinfunction "2_2") (pintype "passive"))
    )
    (net (code "36") (name "Net-(J1-D+-PadA6)") (class "Default")
      (node (ref "J1") (pin "A6") (pinfunction "D+_A6") (pintype "bidirectional"))
      (node (ref "J1") (pin "B6") (pinfunction "D+_B6") (pintype "bidirectional"))
      (node (ref "R12") (pin "1") (pinfunction "1_1") (pintype "passive"))
    )
    (net (code "37") (name "Net-(J1-D--PadA7)") (class "Default")
      (node (ref "J1") (pin "A7") (pinfunction "D-_A7") (pintype "bidirectional"))
      (node (ref "J1") (pin "B7") (pinfunction "D-_B7") (pintype "bidirectional"))
      (node (ref "R11") (pin "1") (pinfunction "1_1") (pintype "passive"))
    )
    (net (code "38") (name "Net-(R2-Pad1)") (class "Default")
      (node (ref "R2") (pin "1") (pinfunction "1_1") (pintype "passive"))
      (node (ref "U$3") (pin "D") (pinfunction "D_D") (pintype "passive"))
    )
    (net (code "39") (name "Net-(R3-Pad2)") (class "Default")
      (node (ref "R3") (pin "2") (pinfunction "2_2") (pintype "passive"))
      (node (ref "U$5") (pin "A") (pinfunction "A_A") (pintype "bidirectional"))
    )
    (net (code "40") (name "Net-(U7-CT)") (class "Default")
      (node (ref "C23") (pin "2") (pinfunction "2_2") (pintype "passive"))
      (node (ref "U7") (pin "4") (pinfunction "CT_4") (pintype "output"))
    )
    (net (code "41") (name "Net-(U7-QOD)") (class "Default")
      (node (ref "R21") (pin "1") (pinfunction "1_1") (pintype "passive"))
      (node (ref "U7") (pin "5") (pinfunction "QOD_5") (pintype "input"))
    )
    (net (code "42") (name "Net-(U8A-ILIM)") (class "Default")
      (node (ref "R22") (pin "2") (pinfunction "2_2") (pintype "passive"))
      (node (ref "U8") (pin "12") (pinfunction "ILIM_12") (pintype "passive"))
    )
    (net (code "43") (name "Net-(U8A-TS{slash}CTRL)") (class "Default")
      (node (ref "R6") (pin "2") (pinfunction "2_2") (pintype "passive"))
      (node (ref "U8") (pin "13") (pinfunction "TS/CTRL_13") (pintype "input"))
    )
    (net (code "44") (name "Net-(U8A-~{CHG})") (class "Default")
      (node (ref "R25") (pin "2") (pinfunction "2_2") (pintype "passive"))
      (node (ref "U8") (pin "7") (pinfunction "~{CHG}_7") (pintype "output"))
    )
    (net (code "45") (name "Net-(Y1-OUT{slash}IN)") (class "Default")
      (node (ref "C17") (pin "1") (pinfunction "1_1") (pintype "passive"))
      (node (ref "R8") (pin "1") (pinfunction "1_1") (pintype "passive"))
      (node (ref "Y1") (pin "3") (pinfunction "OUT/IN_3") (pintype "bidirectional"))
    )
    (net (code "46") (name "QSPI_SS_N") (class "Default")
      (node (ref "R3") (pin "1") (pinfunction "1_1") (pintype "passive"))
      (node (ref "R5") (pin "1") (pinfunction "1_1") (pintype "passive"))
      (node (ref "U$1") (pin "P56") (pinfunction "QSPI_SS_N_P56") (pintype "bidirectional"))
      (node (ref "U4") (pin "1") (pinfunction "/CS_1") (pintype "passive"))
    )
    (net (code "47") (name "RECT") (class "Default")
      (node (ref "C14") (pin "1") (pinfunction "1_1") (pintype "passive"))
      (node (ref "C15") (pin "1") (pinfunction "1_1") (pintype "passive"))
      (node (ref "C34") (pin "1") (pinfunction "1_1") (pintype "passive"))
      (node (ref "R24") (pin "2") (pinfunction "2_2") (pintype "passive"))
      (node (ref "U8") (pin "18") (pinfunction "RECT_18") (pintype "output"))
    )
    (net (code "48") (name "RESET") (class "Default")
      (node (ref "R4") (pin "1") (pinfunction "1_1") (pintype "passive"))
      (node (ref "U$1") (pin "P26") (pinfunction "RUN_P26") (pintype "bidirectional"))
      (node (ref "U$4") (pin "A") (pinfunction "A_A") (pintype "bidirectional"))
    )
    (net (code "49") (name "RESET_D") (class "Default")
      (node (ref "R9") (pin "1") (pinfunction "1_1") (pintype "passive"))
      (node (ref "U$1") (pin "P2") (pinfunction "GPIO0_P2") (pintype "bidirectional"))
      (node (ref "U3") (pin "1") (pinfunction "~{OUT}_1") (pintype "output"))
      (node (ref "X1") (pin "18") (pinfunction "1_18") (pintype "passive"))
    )
    (net (code "50") (name "SCK") (class "Default")
      (node (ref "U$1") (pin "P4") (pinfunction "GPIO2_P4") (pintype "bidirectional"))
      (node (ref "X1") (pin "16") (pinfunction "1_16") (pintype "passive"))
    )
    (net (code "51") (name "SCL") (class "Default")
      (node (ref "R15") (pin "1") (pinfunction "1_1") (pintype "passive"))
      (node (ref "U$1") (pin "P16") (pinfunction "GPIO13_P16") (pintype "bidirectional"))
      (node (ref "U6") (pin "8") (pinfunction "SCL_8") (pintype "passive"))
    )
    (net (code "52") (name "SD0") (class "Default")
      (node (ref "U$1") (pin "P53") (pinfunction "QSPI_SD0_P53") (pintype "bidirectional"))
      (node (ref "U4") (pin "5") (pinfunction "DI(IO0)_5") (pintype "passive"))
    )
    (net (code "53") (name "SD1") (class "Default")
      (node (ref "U$1") (pin "P55") (pinfunction "QSPI_SD1_P55") (pintype "bidirectional"))
      (node (ref "U4") (pin "2") (pinfunction "DO(IO1)_2") (pintype "passive"))
    )
    (net (code "54") (name "SD2") (class "Default")
      (node (ref "U$1") (pin "P54") (pinfunction "QSPI_SD2_P54") (pintype "bidirectional"))
      (node (ref "U4") (pin "3") (pinfunction "/WP(IO2)_3") (pintype "passive"))
    )
    (net (code "55") (name "SD3") (class "Default")
      (node (ref "U$1") (pin "P51") (pinfunction "QSPI_SD3_P51") (pintype "bidirectional"))
      (node (ref "U4") (pin "7") (pinfunction "/HOLD_OR_/RESET(IO3)_7") (pintype "passive"))
    )
    (net (code "56") (name "SDA") (class "Default")
      (node (ref "R16") (pin "1") (pinfunction "1_1") (pintype "passive"))
      (node (ref "U$1") (pin "P15") (pinfunction "GPIO12_P15") (pintype "bidirectional"))
      (node (ref "U6") (pin "1") (pinfunction "SDA_1") (pintype "passive"))
    )
    (net (code "57") (name "TERM") (class "Default")
      (node (ref "R7") (pin "2") (pinfunction "2_2") (pintype "passive"))
      (node (ref "U8") (pin "10") (pinfunction "TERM_10") (pintype "input"))
    )
    (net (code "58") (name "TFT_CS") (class "Default")
      (node (ref "R10") (pin "1") (pinfunction "1_1") (pintype "passive"))
      (node (ref "U$1") (pin "P3") (pinfunction "GPIO1_P3") (pintype "bidirectional"))
      (node (ref "X1") (pin "17") (pinfunction "1_17") (pintype "passive"))
    )
    (net (code "59") (name "TFT_DC") (class "Default")
      (node (ref "U$1") (pin "P6") (pinfunction "GPIO4_P6") (pintype "bidirectional"))
      (node (ref "X1") (pin "15") (pinfunction "1_15") (pintype "passive"))
    )
    (net (code "60") (name "TFT_PWR") (class "Default")
      (node (ref "U$1") (pin "P32") (pinfunction "GPIO21_P32") (pintype "bidirectional"))
      (node (ref "U7") (pin "3") (pinfunction "ON_3") (pintype "input"))
    )
    (net (code "61") (name "VBAT") (class "Default")
      (node (ref "BAT_POS") (pin "1") (pinfunction "P_1") (pintype "passive"))
      (node (ref "C32") (pin "1") (pinfunction "1_1") (pintype "passive"))
      (node (ref "C33") (pin "1") (pinfunction "1_1") (pintype "passive"))
      (node (ref "D1") (pin "A") (pinfunction "A_A") (pintype "passive"))
      (node (ref "U5") (pin "3") (pinfunction "D_3") (pintype "output"))
      (node (ref "U8") (pin "11") (pinfunction "EN2_11") (pintype "input"))
      (node (ref "U8") (pin "4") (pinfunction "BAT_4") (pintype "output"))
    )
    (net (code "62") (name "VUSB") (class "Default")
      (node (ref "J1") (pin "VBUS1") (pinfunction "VBUS_VBUS1") (pintype "bidirectional"))
      (node (ref "J1") (pin "VBUS2") (pinfunction "VBUS_VBUS2") (pintype "bidirectional"))
      (node (ref "U$2") (pin "2") (pinfunction "A_2") (pintype "passive"))
      (node (ref "U5") (pin "1") (pinfunction "G_1") (pintype "power_in"))
    )
    (net (code "63") (name "XIN") (class "Default")
      (node (ref "C16") (pin "1") (pinfunction "1_1") (pintype "passive"))
      (node (ref "U$1") (pin "P20") (pinfunction "XIN_P20") (pintype "bidirectional"))
      (node (ref "Y1") (pin "1") (pinfunction "IN/OUT_1") (pintype "bidirectional"))
    )
    (net (code "64") (name "XOUT") (class "Default")
      (node (ref "R8") (pin "2") (pinfunction "2_2") (pintype "passive"))
      (node (ref "U$1") (pin "P21") (pinfunction "XOUT_P21") (pintype "bidirectional"))
    )
    (net (code "65") (name "unconnected-(U$1-GPIO6-PadP8)") (class "Default")
      (node (ref "U$1") (pin "P8") (pinfunction "GPIO6_P8") (pintype "bidirectional"))
    )
    (net (code "66") (name "unconnected-(U$1-GPIO7-PadP9)") (class "Default")
      (node (ref "U$1") (pin "P9") (pinfunction "GPIO7_P9") (pintype "bidirectional"))
    )
    (net (code "67") (name "unconnected-(U$1-GPIO8-PadP11)") (class "Default")
      (node (ref "U$1") (pin "P11") (pinfunction "GPIO8_P11") (pintype "bidirectional"))
    )
    (net (code "68") (name "unconnected-(U$1-GPIO9-PadP12)") (class "Default")
      (node (ref "U$1") (pin "P12") (pinfunction "GPIO9_P12") (pintype "bidirectional"))
    )
    (net (code "69") (name "unconnected-(U$1-GPIO15-PadP18)") (class "Default")
      (node (ref "U$1") (pin "P18") (pinfunction "GPIO15_P18") (pintype "bidirectional"))
    )
    (net (code "70") (name "unconnected-(U$1-GPIO16-PadP27)") (class "Default")
      (node (ref "U$1") (pin "P27") (pinfunction "GPIO16_P27") (pintype "bidirectional"))
    )
    (net (code "71") (name "unconnected-(U$1-GPIO17-PadP28)") (class "Default")
      (node (ref "U$1") (pin "P28") (pinfunction "GPIO17_P28") (pintype "bidirectional"))
    )
    (net (code "72") (name "unconnected-(U$1-GPIO19-PadP30)") (class "Default")
      (node (ref "U$1") (pin "P30") (pinfunction "GPIO19_P30") (pintype "bidirectional"))
    )
    (net (code "73") (name "unconnected-(U$1-GPIO20-PadP31)") (class "Default")
      (node (ref "U$1") (pin "P31") (pinfunction "GPIO20_P31") (pintype "bidirectional"))
    )
    (net (code "74") (name "unconnected-(U$1-GPIO22-PadP34)") (class "Default")
      (node (ref "U$1") (pin "P34") (pinfunction "GPIO22_P34") (pintype "bidirectional"))
    )
    (net (code "75") (name "unconnected-(U$1-SWCLK-PadP24)") (class "Default")
      (node (ref "U$1") (pin "P24") (pinfunction "SWCLK_P24") (pintype "bidirectional"))
    )
    (net (code "76") (name "unconnected-(U$1-SWDIO-PadP25)") (class "Default")
      (node (ref "U$1") (pin "P25") (pinfunction "SWDIO_P25") (pintype "bidirectional"))
    )
    (net (code "77") (name "unconnected-(U2-NC-Pad4)") (class "Default")
      (node (ref "U2") (pin "4") (pinfunction "NC_4") (pintype "no_connect"))
    )
    (net (code "78") (name "unconnected-(U6-NC-Pad7)") (class "Default")
      (node (ref "U6") (pin "7") (pinfunction "NC_7") (pintype "no_connect"))
    )
    (net (code "79") (name "unconnected-(U6-NC_2-Pad4)") (class "Default")
      (node (ref "U6") (pin "4") (pinfunction "NC_2_4") (pintype "no_connect"))
    )
    (net (code "80") (name "unconnected-(U8A-~{AD-EN}-Pad8)") (class "Default")
      (node (ref "U8") (pin "8") (pinfunction "~{AD-EN}_8") (pintype "output"))
    )
    (net (code "81") (name "unconnected-(X1R-1-Pad3)") (class "Default")
      (node (ref "X1") (pin "3") (pinfunction "1_3") (pintype "passive"))
    )
    (net (code "82") (name "unconnected-(X1S-1-Pad4)") (class "Default")
      (node (ref "X1") (pin "4") (pinfunction "1_4") (pintype "passive"))
    )
  )
)
